# PROB_S7CAS_Title.net
KiCad netlist of a schematic drawn in Altium Designer
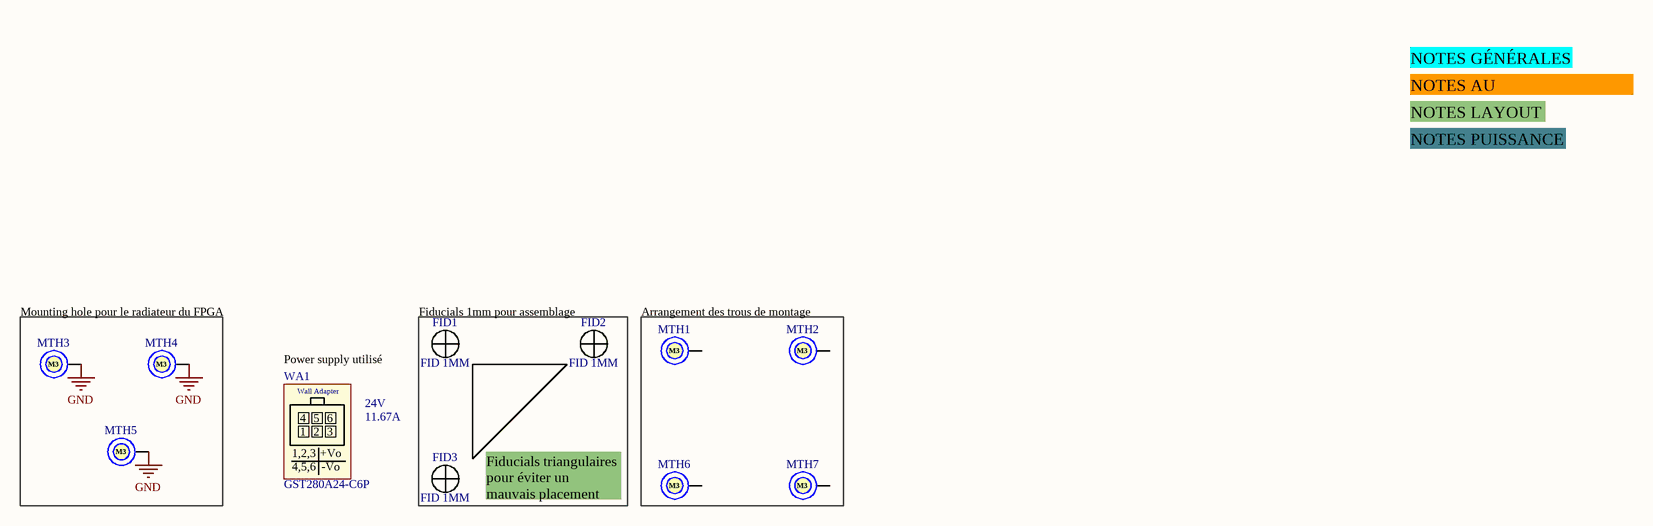
[diagram p0: PROB_S7CAS_Title.SchDoc]

(export (version "E")
  (design (tool "Eeschema 10.0.6"))
  (components
    (comp (ref "FID1")
      (value "FID 1MM")
      (footprint "FID_CIRCLE_1MM")
      (description "FID - FIDUCIAL 1MM CIRCLE DOUBLE-SIDED - 1MM")
      (fields
        (field (name "CREATEDBY/DATE") "Jonathan Bouchard 2018-07-23")
        (field (name "VERIFIEDBY") "Caroline Paulin - 25 juillet 2018")
      )
      (libsource (lib "S7CAS_LIB2021") (part "FID_CIRCLE_1MM"))
    )
    (comp (ref "FID2")
      (value "FID 1MM")
      (footprint "FID_CIRCLE_1MM")
      (description "FID - FIDUCIAL 1MM CIRCLE DOUBLE-SIDED - 1MM")
      (fields
        (field (name "CREATEDBY/DATE") "Jonathan Bouchard 2018-07-23")
        (field (name "VERIFIEDBY") "Caroline Paulin - 25 juillet 2018")
      )
      (libsource (lib "S7CAS_LIB2021") (part "FID_CIRCLE_1MM"))
    )
    (comp (ref "FID3")
      (value "FID 1MM")
      (footprint "FID_CIRCLE_1MM")
      (description "FID - FIDUCIAL 1MM CIRCLE DOUBLE-SIDED - 1MM")
      (fields
        (field (name "CREATEDBY/DATE") "Jonathan Bouchard 2018-07-23")
        (field (name "VERIFIEDBY") "Caroline Paulin - 25 juillet 2018")
      )
      (libsource (lib "S7CAS_LIB2021") (part "FID_CIRCLE_1MM"))
    )
    (comp (ref "MTH1")
      (value "M3")
      (footprint "MTH_M3")
      (description "MTH - MOUNTING HOLE M3 PLATED - M3")
      (fields
        (field (name "CREATEDBY/DATE") "Jonathan Bouchard 2018-07-23")
        (field (name "VERIFIEDBY") "Arnaud Samson 23-07-18")
      )
      (libsource (lib "S7CAS_LIB2021") (part "MTH_M3"))
    )
    (comp (ref "MTH2")
      (value "M3")
      (footprint "MTH_M3")
      (description "MTH - MOUNTING HOLE M3 PLATED - M3")
      (fields
        (field (name "CREATEDBY/DATE") "Jonathan Bouchard 2018-07-23")
        (field (name "VERIFIEDBY") "Arnaud Samson 23-07-18")
      )
      (libsource (lib "S7CAS_LIB2021") (part "MTH_M3"))
    )
    (comp (ref "MTH3")
      (value "M3")
      (footprint "MTH_M3")
      (description "MTH - MOUNTING HOLE M3 PLATED - M3")
      (fields
        (field (name "CREATEDBY/DATE") "Jonathan Bouchard 2018-07-23")
        (field (name "VERIFIEDBY") "Arnaud Samson 23-07-18")
      )
      (libsource (lib "S7CAS_LIB2021") (part "MTH_M3"))
    )
    (comp (ref "MTH4")
      (value "M3")
      (footprint "MTH_M3")
      (description "MTH - MOUNTING HOLE M3 PLATED - M3")
      (fields
        (field (name "CREATEDBY/DATE") "Jonathan Bouchard 2018-07-23")
        (field (name "VERIFIEDBY") "Arnaud Samson 23-07-18")
      )
      (libsource (lib "S7CAS_LIB2021") (part "MTH_M3"))
    )
    (comp (ref "MTH5")
      (value "M3")
      (footprint "MTH_M3")
      (description "MTH - MOUNTING HOLE M3 PLATED - M3")
      (fields
        (field (name "CREATEDBY/DATE") "Jonathan Bouchard 2018-07-23")
        (field (name "VERIFIEDBY") "Arnaud Samson 23-07-18")
      )
      (libsource (lib "S7CAS_LIB2021") (part "MTH_M3"))
    )
    (comp (ref "MTH6")
      (value "M3")
      (footprint "MTH_M3")
      (description "MTH - MOUNTING HOLE M3 PLATED - M3")
      (fields
        (field (name "CREATEDBY/DATE") "Jonathan Bouchard 2018-07-23")
        (field (name "VERIFIEDBY") "Arnaud Samson 23-07-18")
      )
      (libsource (lib "S7CAS_LIB2021") (part "MTH_M3"))
    )
    (comp (ref "MTH7")
      (value "M3")
      (footprint "MTH_M3")
      (description "MTH - MOUNTING HOLE M3 PLATED - M3")
      (fields
        (field (name "CREATEDBY/DATE") "Jonathan Bouchard 2018-07-23")
        (field (name "VERIFIEDBY") "Arnaud Samson 23-07-18")
      )
      (libsource (lib "S7CAS_LIB2021") (part "MTH_M3"))
    )
    (comp (ref "WA1")
      (value "GST280A24-C6P")
      (footprint "Model Name")
      (description "UND - AC/DC DESKTOP ADAPTER 24V 280W - MEC")
      (fields
        (field (name "TOLERANCE") "±3%")
        (field (name "CURRENT RATING") "11.67A")
        (field (name "ALTIUM_VALUE") "24V")
        (field (name "CREATEDBY/DATE") "Caroline Paulin - 5 avril 2019")
        (field (name "VERIFIEDBY") "Nicolas V. (2019-07-05)")
      )
      (libsource (lib "S7CAS_LIB2021") (part "UND_GST280A24-C6P"))
    )
  )
  (nets
    (net (code "1") (name "GND") (class "Default")
      (node (ref "MTH3") (pin "1") (pinfunction "1_1") (pintype "passive"))
      (node (ref "MTH4") (pin "1") (pinfunction "1_1") (pintype "passive"))
      (node (ref "MTH5") (pin "1") (pinfunction "1_1") (pintype "passive"))
    )
    (net (code "2") (name "unconnected-(FID1-Pad1)") (class "Default")
      (node (ref "FID1") (pin "1") (pinfunction "1_1") (pintype "passive"))
    )
    (net (code "3") (name "unconnected-(FID1-Pad2)") (class "Default")
      (node (ref "FID1") (pin "2") (pinfunction "2_2") (pintype "passive"))
    )
    (net (code "4") (name "unconnected-(FID2-Pad1)") (class "Default")
      (node (ref "FID2") (pin "1") (pinfunction "1_1") (pintype "passive"))
    )
    (net (code "5") (name "unconnected-(FID2-Pad2)") (class "Default")
      (node (ref "FID2") (pin "2") (pinfunction "2_2") (pintype "passive"))
    )
    (net (code "6") (name "unconnected-(FID3-Pad1)") (class "Default")
      (node (ref "FID3") (pin "1") (pinfunction "1_1") (pintype "passive"))
    )
    (net (code "7") (name "unconnected-(FID3-Pad2)") (class "Default")
      (node (ref "FID3") (pin "2") (pinfunction "2_2") (pintype "passive"))
    )
    (net (code "8") (name "unconnected-(MTH1-Pad1)") (class "Default")
      (node (ref "MTH1") (pin "1") (pinfunction "1_1") (pintype "passive"))
    )
    (net (code "9") (name "unconnected-(MTH2-Pad1)") (class "Default")
      (node (ref "MTH2") (pin "1") (pinfunction "1_1") (pintype "passive"))
    )
    (net (code "10") (name "unconnected-(MTH6-Pad1)") (class "Default")
      (node (ref "MTH6") (pin "1") (pinfunction "1_1") (pintype "passive"))
    )
    (net (code "11") (name "unconnected-(MTH7-Pad1)") (class "Default")
      (node (ref "MTH7") (pin "1") (pinfunction "1_1") (pintype "passive"))
    )
  )
)
